# Base-Shield-v2.net
KiCad netlist of a schematic drawn in EAGLE
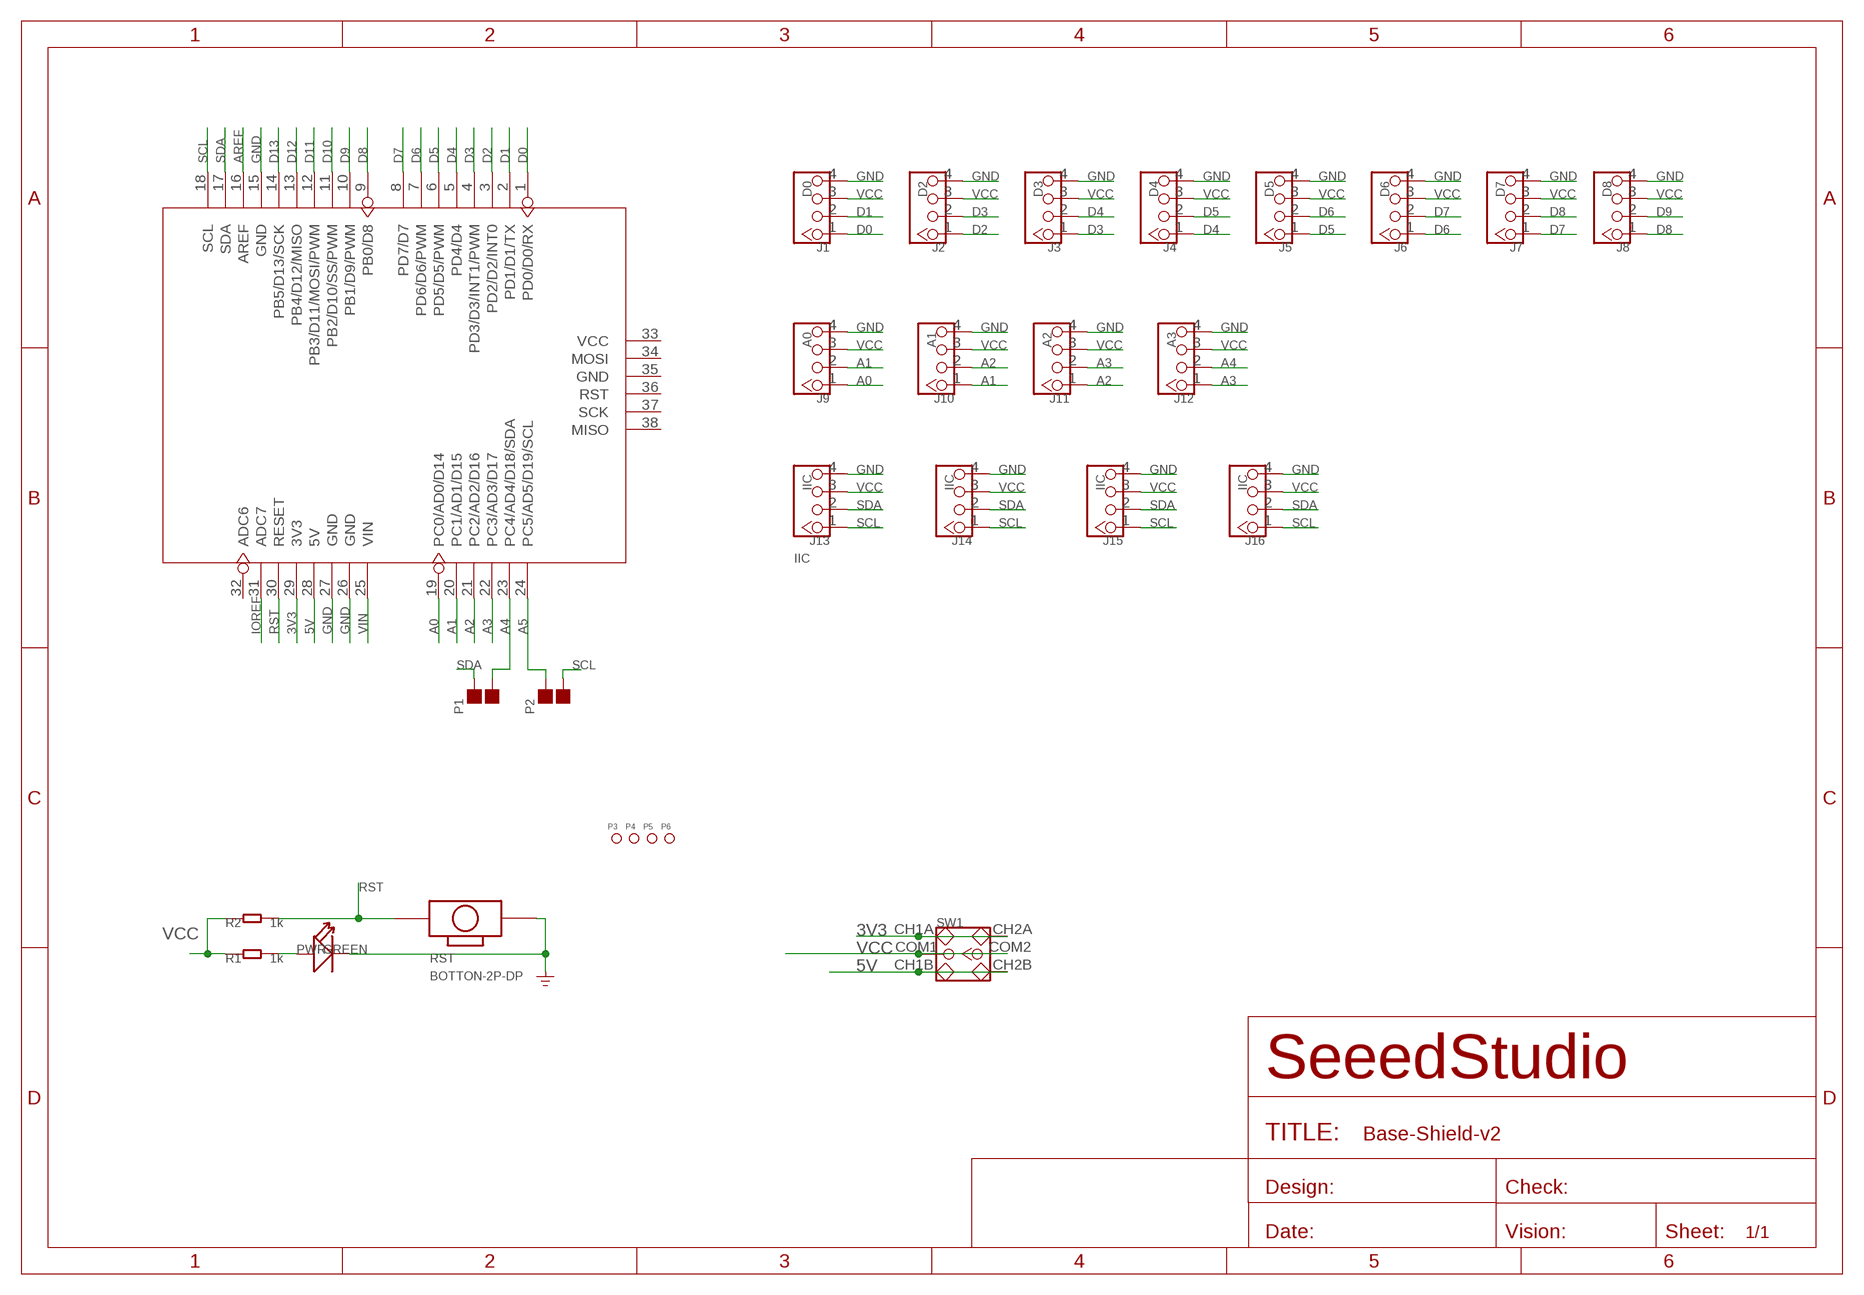
[diagram p0: schematic, sheet 1]

(export (version "E")
  (design (tool "Eeschema 10.0.6"))
  (components
    (comp (ref "J1")
      (value "D0")
      (footprint "eagle-import:4P-2.0")
      (libsource (lib "eagle-import") (part "TWIG-4P-2.0-2.0"))
    )
    (comp (ref "J2")
      (value "D2")
      (footprint "eagle-import:4P-2.0")
      (libsource (lib "eagle-import") (part "TWIG-4P-2.0-2.0"))
    )
    (comp (ref "J3")
      (value "D3")
      (footprint "eagle-import:4P-2.0")
      (libsource (lib "eagle-import") (part "TWIG-4P-2.0-2.0"))
    )
    (comp (ref "J4")
      (value "D4")
      (footprint "eagle-import:4P-2.0")
      (libsource (lib "eagle-import") (part "TWIG-4P-2.0-2.0"))
    )
    (comp (ref "J5")
      (value "D5")
      (footprint "eagle-import:4P-2.0")
      (libsource (lib "eagle-import") (part "TWIG-4P-2.0-2.0"))
    )
    (comp (ref "J6")
      (value "D6")
      (footprint "eagle-import:4P-2.0")
      (libsource (lib "eagle-import") (part "TWIG-4P-2.0-2.0"))
    )
    (comp (ref "J7")
      (value "D7")
      (footprint "eagle-import:4P-2.0")
      (libsource (lib "eagle-import") (part "TWIG-4P-2.0-2.0"))
    )
    (comp (ref "J8")
      (value "D8")
      (footprint "eagle-import:4P-2.0")
      (libsource (lib "eagle-import") (part "TWIG-4P-2.0-2.0"))
    )
    (comp (ref "J9")
      (value "A0")
      (footprint "eagle-import:4P-2.0-90D")
      (libsource (lib "eagle-import") (part "TWIG-4P-2.0'90D'"))
    )
    (comp (ref "J10")
      (value "A1")
      (footprint "eagle-import:4P-2.0-90D")
      (libsource (lib "eagle-import") (part "TWIG-4P-2.0'90D'"))
    )
    (comp (ref "J11")
      (value "A2")
      (footprint "eagle-import:4P-2.0-90D")
      (libsource (lib "eagle-import") (part "TWIG-4P-2.0'90D'"))
    )
    (comp (ref "J12")
      (value "A3")
      (footprint "eagle-import:4P-2.0-90D")
      (libsource (lib "eagle-import") (part "TWIG-4P-2.0'90D'"))
    )
    (comp (ref "J13")
      (value "IIC")
      (footprint "eagle-import:4P-2.0")
      (libsource (lib "eagle-import") (part "TWIG-4P-2.0-2.0"))
    )
    (comp (ref "J14")
      (value "IIC")
      (footprint "eagle-import:4P-2.0")
      (libsource (lib "eagle-import") (part "TWIG-4P-2.0-2.0"))
    )
    (comp (ref "J15")
      (value "IIC")
      (footprint "eagle-import:4P-2.0")
      (libsource (lib "eagle-import") (part "TWIG-4P-2.0-2.0"))
    )
    (comp (ref "J16")
      (value "IIC")
      (footprint "eagle-import:4P-2.0")
      (libsource (lib "eagle-import") (part "TWIG-4P-2.0-2.0"))
    )
    (comp (ref "P1")
      (value "DNP")
      (footprint "eagle-import:2P-SMD-1.78X1.27")
      (libsource (lib "eagle-import") (part "PAD-JUMPER-2P"))
    )
    (comp (ref "P2")
      (value "DNP")
      (footprint "eagle-import:2P-SMD-1.78X1.27")
      (libsource (lib "eagle-import") (part "PAD-JUMPER-2P"))
    )
    (comp (ref "P3")
      (value "PAD-MARK")
      (footprint "eagle-import:ROUND-MARK-1.0")
      (fields (field (name "PARTNO") "DNP"))
      (libsource (lib "eagle-import") (part "PAD-MARK"))
    )
    (comp (ref "P4")
      (value "PAD-MARK")
      (footprint "eagle-import:ROUND-MARK-1.0")
      (fields (field (name "PARTNO") "DNP"))
      (libsource (lib "eagle-import") (part "PAD-MARK"))
    )
    (comp (ref "P5")
      (value "PAD-MARK")
      (footprint "eagle-import:ROUND-MARK-1.0")
      (fields (field (name "PARTNO") "DNP"))
      (libsource (lib "eagle-import") (part "PAD-MARK"))
    )
    (comp (ref "P6")
      (value "PAD-MARK")
      (footprint "eagle-import:ROUND-MARK-1.0")
      (fields (field (name "PARTNO") "DNP"))
      (libsource (lib "eagle-import") (part "PAD-MARK"))
    )
    (comp (ref "PWR")
      (value "GREEN")
      (footprint "eagle-import:LED-2P-2.54-3MM")
      (libsource (lib "eagle-import") (part "LED-3MM"))
    )
    (comp (ref "R1")
      (value "1k")
      (footprint "eagle-import:R0603")
      (libsource (lib "eagle-import") (part "R-0603"))
    )
    (comp (ref "R2")
      (value "1k")
      (footprint "eagle-import:R0603")
      (libsource (lib "eagle-import") (part "R-0603"))
    )
    (comp (ref "RST")
      (value "BOTTON-2P-DP")
      (footprint "eagle-import:2P-7.62X3.56-90D")
      (libsource (lib "eagle-import") (part "BOTTON-2P-90"))
    )
    (comp (ref "SW1")
      (value "SWITCH-2CH-6P'90D'")
      (footprint "eagle-import:6P-2CH-2.5-9.1X3.5X3.2H-90D")
      (libsource (lib "eagle-import") (part "SWITCH-2CH-6P'90D'"))
    )
    (comp (ref "U2")
      (value "DIP Long Blue Female Header")
      (footprint "eagle-import:ARDUINO-38P")
      (libsource (lib "eagle-import") (part "ARDUINO-38P"))
    )
  )
  (nets
    (net (code "1") (name "/3V3") (class "Default")
      (node (ref "SW1") (pin "CH1A") (pinfunction "CH1A_CH1A") (pintype "bidirectional"))
      (node (ref "SW1") (pin "CH2A") (pinfunction "CH2A_CH2A") (pintype "bidirectional"))
      (node (ref "U2") (pin "29") (pinfunction "3V3_29") (pintype "bidirectional"))
    )
    (net (code "2") (name "/5V") (class "Default")
      (node (ref "SW1") (pin "CH1B") (pinfunction "CH1B_CH1B") (pintype "bidirectional"))
      (node (ref "SW1") (pin "CH2B") (pinfunction "CH2B_CH2B") (pintype "bidirectional"))
      (node (ref "U2") (pin "28") (pinfunction "5V_28") (pintype "bidirectional"))
    )
    (net (code "3") (name "/A0") (class "Default")
      (node (ref "J9") (pin "1") (pinfunction "1_1") (pintype "bidirectional"))
      (node (ref "U2") (pin "19") (pinfunction "PC0/AD0/D14_19") (pintype "bidirectional"))
    )
    (net (code "4") (name "/A1") (class "Default")
      (node (ref "J10") (pin "1") (pinfunction "1_1") (pintype "bidirectional"))
      (node (ref "J9") (pin "2") (pinfunction "2_2") (pintype "bidirectional"))
      (node (ref "U2") (pin "20") (pinfunction "PC1/AD1/D15_20") (pintype "bidirectional"))
    )
    (net (code "5") (name "/A2") (class "Default")
      (node (ref "J10") (pin "2") (pinfunction "2_2") (pintype "bidirectional"))
      (node (ref "J11") (pin "1") (pinfunction "1_1") (pintype "bidirectional"))
      (node (ref "U2") (pin "21") (pinfunction "PC2/AD2/D16_21") (pintype "bidirectional"))
    )
    (net (code "6") (name "/A3") (class "Default")
      (node (ref "J11") (pin "2") (pinfunction "2_2") (pintype "bidirectional"))
      (node (ref "J12") (pin "1") (pinfunction "1_1") (pintype "bidirectional"))
      (node (ref "U2") (pin "22") (pinfunction "PC3/AD3/D17_22") (pintype "bidirectional"))
    )
    (net (code "7") (name "/A4") (class "Default")
      (node (ref "J12") (pin "2") (pinfunction "2_2") (pintype "bidirectional"))
      (node (ref "P1") (pin "1") (pinfunction "1_1") (pintype "bidirectional"))
      (node (ref "U2") (pin "23") (pinfunction "PC4/AD4/D18/SDA_23") (pintype "bidirectional"))
    )
    (net (code "8") (name "/A5") (class "Default")
      (node (ref "P2") (pin "2") (pinfunction "2_2") (pintype "bidirectional"))
      (node (ref "U2") (pin "24") (pinfunction "PC5/AD5/D19/SCL_24") (pintype "bidirectional"))
    )
    (net (code "9") (name "/AREF") (class "Default")
      (node (ref "U2") (pin "16") (pinfunction "AREF_16") (pintype "bidirectional"))
    )
    (net (code "10") (name "/D0") (class "Default")
      (node (ref "J1") (pin "1") (pinfunction "1_1") (pintype "bidirectional"))
      (node (ref "U2") (pin "1") (pinfunction "PD0/D0/RX_1") (pintype "bidirectional"))
    )
    (net (code "11") (name "/D1") (class "Default")
      (node (ref "J1") (pin "2") (pinfunction "2_2") (pintype "bidirectional"))
      (node (ref "U2") (pin "2") (pinfunction "PD1/D1/TX_2") (pintype "bidirectional"))
    )
    (net (code "12") (name "/D2") (class "Default")
      (node (ref "J2") (pin "1") (pinfunction "1_1") (pintype "bidirectional"))
      (node (ref "U2") (pin "3") (pinfunction "PD2/D2/INT0_3") (pintype "bidirectional"))
    )
    (net (code "13") (name "/D3") (class "Default")
      (node (ref "J2") (pin "2") (pinfunction "2_2") (pintype "bidirectional"))
      (node (ref "J3") (pin "1") (pinfunction "1_1") (pintype "bidirectional"))
      (node (ref "U2") (pin "4") (pinfunction "PD3/D3/INT1/PWM_4") (pintype "bidirectional"))
    )
    (net (code "14") (name "/D4") (class "Default")
      (node (ref "J3") (pin "2") (pinfunction "2_2") (pintype "bidirectional"))
      (node (ref "J4") (pin "1") (pinfunction "1_1") (pintype "bidirectional"))
      (node (ref "U2") (pin "5") (pinfunction "PD4/D4_5") (pintype "bidirectional"))
    )
    (net (code "15") (name "/D5") (class "Default")
      (node (ref "J4") (pin "2") (pinfunction "2_2") (pintype "bidirectional"))
      (node (ref "J5") (pin "1") (pinfunction "1_1") (pintype "bidirectional"))
      (node (ref "U2") (pin "6") (pinfunction "PD5/D5/PWM_6") (pintype "bidirectional"))
    )
    (net (code "16") (name "/D6") (class "Default")
      (node (ref "J5") (pin "2") (pinfunction "2_2") (pintype "bidirectional"))
      (node (ref "J6") (pin "1") (pinfunction "1_1") (pintype "bidirectional"))
      (node (ref "U2") (pin "7") (pinfunction "PD6/D6/PWM_7") (pintype "bidirectional"))
    )
    (net (code "17") (name "/D7") (class "Default")
      (node (ref "J6") (pin "2") (pinfunction "2_2") (pintype "bidirectional"))
      (node (ref "J7") (pin "1") (pinfunction "1_1") (pintype "bidirectional"))
      (node (ref "U2") (pin "8") (pinfunction "PD7/D7_8") (pintype "bidirectional"))
    )
    (net (code "18") (name "/D8") (class "Default")
      (node (ref "J7") (pin "2") (pinfunction "2_2") (pintype "bidirectional"))
      (node (ref "J8") (pin "1") (pinfunction "1_1") (pintype "bidirectional"))
      (node (ref "U2") (pin "9") (pinfunction "PB0/D8_9") (pintype "bidirectional"))
    )
    (net (code "19") (name "/D9") (class "Default")
      (node (ref "J8") (pin "2") (pinfunction "2_2") (pintype "bidirectional"))
      (node (ref "U2") (pin "10") (pinfunction "PB1/D9/PWM_10") (pintype "bidirectional"))
    )
    (net (code "20") (name "/D10") (class "Default")
      (node (ref "U2") (pin "11") (pinfunction "PB2/D10/SS/PWM_11") (pintype "bidirectional"))
    )
    (net (code "21") (name "/D11") (class "Default")
      (node (ref "U2") (pin "12") (pinfunction "PB3/D11/MOSI/PWM_12") (pintype "bidirectional"))
    )
    (net (code "22") (name "/D12") (class "Default")
      (node (ref "U2") (pin "13") (pinfunction "PB4/D12/MISO_13") (pintype "bidirectional"))
    )
    (net (code "23") (name "/D13") (class "Default")
      (node (ref "U2") (pin "14") (pinfunction "PB5/D13/SCK_14") (pintype "bidirectional"))
    )
    (net (code "24") (name "/IOREF") (class "Default")
      (node (ref "U2") (pin "31") (pinfunction "ADC7_31") (pintype "bidirectional"))
    )
    (net (code "25") (name "/RST") (class "Default")
      (node (ref "R2") (pin "2") (pinfunction "2_2") (pintype "passive"))
      (node (ref "RST") (pin "P$1") (pinfunction "1_P$1") (pintype "bidirectional"))
      (node (ref "U2") (pin "30") (pinfunction "RESET_30") (pintype "bidirectional"))
    )
    (net (code "26") (name "/SCL") (class "Default")
      (node (ref "J13") (pin "1") (pinfunction "1_1") (pintype "bidirectional"))
      (node (ref "J14") (pin "1") (pinfunction "1_1") (pintype "bidirectional"))
      (node (ref "J15") (pin "1") (pinfunction "1_1") (pintype "bidirectional"))
      (node (ref "J16") (pin "1") (pinfunction "1_1") (pintype "bidirectional"))
      (node (ref "P2") (pin "1") (pinfunction "1_1") (pintype "bidirectional"))
      (node (ref "U2") (pin "18") (pinfunction "SCL_18") (pintype "bidirectional"))
    )
    (net (code "27") (name "/SDA") (class "Default")
      (node (ref "J13") (pin "2") (pinfunction "2_2") (pintype "bidirectional"))
      (node (ref "J14") (pin "2") (pinfunction "2_2") (pintype "bidirectional"))
      (node (ref "J15") (pin "2") (pinfunction "2_2") (pintype "bidirectional"))
      (node (ref "J16") (pin "2") (pinfunction "2_2") (pintype "bidirectional"))
      (node (ref "P1") (pin "2") (pinfunction "2_2") (pintype "bidirectional"))
      (node (ref "U2") (pin "17") (pinfunction "SDA_17") (pintype "bidirectional"))
    )
    (net (code "28") (name "/VCC") (class "Default")
      (node (ref "J1") (pin "3") (pinfunction "3_3") (pintype "bidirectional"))
      (node (ref "J10") (pin "3") (pinfunction "3_3") (pintype "bidirectional"))
      (node (ref "J11") (pin "3") (pinfunction "3_3") (pintype "bidirectional"))
      (node (ref "J12") (pin "3") (pinfunction "3_3") (pintype "bidirectional"))
      (node (ref "J13") (pin "3") (pinfunction "3_3") (pintype "bidirectional"))
      (node (ref "J14") (pin "3") (pinfunction "3_3") (pintype "bidirectional"))
      (node (ref "J15") (pin "3") (pinfunction "3_3") (pintype "bidirectional"))
      (node (ref "J16") (pin "3") (pinfunction "3_3") (pintype "bidirectional"))
      (node (ref "J2") (pin "3") (pinfunction "3_3") (pintype "bidirectional"))
      (node (ref "J3") (pin "3") (pinfunction "3_3") (pintype "bidirectional"))
      (node (ref "J4") (pin "3") (pinfunction "3_3") (pintype "bidirectional"))
      (node (ref "J5") (pin "3") (pinfunction "3_3") (pintype "bidirectional"))
      (node (ref "J6") (pin "3") (pinfunction "3_3") (pintype "bidirectional"))
      (node (ref "J7") (pin "3") (pinfunction "3_3") (pintype "bidirectional"))
      (node (ref "J8") (pin "3") (pinfunction "3_3") (pintype "bidirectional"))
      (node (ref "J9") (pin "3") (pinfunction "3_3") (pintype "bidirectional"))
      (node (ref "R1") (pin "1") (pinfunction "1_1") (pintype "passive"))
      (node (ref "R2") (pin "1") (pinfunction "1_1") (pintype "passive"))
      (node (ref "SW1") (pin "COM1") (pinfunction "COM1_COM1") (pintype "bidirectional"))
      (node (ref "SW1") (pin "COM2") (pinfunction "COM2_COM2") (pintype "bidirectional"))
    )
    (net (code "29") (name "/VIN") (class "Default")
      (node (ref "U2") (pin "25") (pinfunction "VIN_25") (pintype "bidirectional"))
    )
    (net (code "30") (name "GND_POWER") (class "Default")
      (node (ref "J1") (pin "4") (pinfunction "4_4") (pintype "bidirectional"))
      (node (ref "J10") (pin "4") (pinfunction "4_4") (pintype "bidirectional"))
      (node (ref "J11") (pin "4") (pinfunction "4_4") (pintype "bidirectional"))
      (node (ref "J12") (pin "4") (pinfunction "4_4") (pintype "bidirectional"))
      (node (ref "J13") (pin "4") (pinfunction "4_4") (pintype "bidirectional"))
      (node (ref "J14") (pin "4") (pinfunction "4_4") (pintype "bidirectional"))
      (node (ref "J15") (pin "4") (pinfunction "4_4") (pintype "bidirectional"))
      (node (ref "J16") (pin "4") (pinfunction "4_4") (pintype "bidirectional"))
      (node (ref "J2") (pin "4") (pinfunction "4_4") (pintype "bidirectional"))
      (node (ref "J3") (pin "4") (pinfunction "4_4") (pintype "bidirectional"))
      (node (ref "J4") (pin "4") (pinfunction "4_4") (pintype "bidirectional"))
      (node (ref "J5") (pin "4") (pinfunction "4_4") (pintype "bidirectional"))
      (node (ref "J6") (pin "4") (pinfunction "4_4") (pintype "bidirectional"))
      (node (ref "J7") (pin "4") (pinfunction "4_4") (pintype "bidirectional"))
      (node (ref "J8") (pin "4") (pinfunction "4_4") (pintype "bidirectional"))
      (node (ref "J9") (pin "4") (pinfunction "4_4") (pintype "bidirectional"))
      (node (ref "PWR") (pin "K") (pinfunction "-_K") (pintype "passive"))
      (node (ref "RST") (pin "P$2") (pinfunction "2_P$2") (pintype "bidirectional"))
      (node (ref "U2") (pin "15") (pinfunction "GND_15") (pintype "bidirectional"))
      (node (ref "U2") (pin "26") (pinfunction "GND_26") (pintype "bidirectional"))
      (node (ref "U2") (pin "27") (pinfunction "GND_27") (pintype "bidirectional"))
    )
    (net (code "31") (name "Net-(PWR-+)") (class "Default")
      (node (ref "PWR") (pin "A") (pinfunction "+_A") (pintype "passive"))
      (node (ref "R1") (pin "2") (pinfunction "2_2") (pintype "passive"))
    )
    (net (code "32") (name "unconnected-(U2-ADC6-Pad32)") (class "Default")
      (node (ref "U2") (pin "32") (pinfunction "ADC6_32") (pintype "bidirectional"))
    )
    (net (code "33") (name "unconnected-(U2-GND-Pad35)") (class "Default")
      (node (ref "U2") (pin "35") (pinfunction "GND_35") (pintype "bidirectional"))
    )
    (net (code "34") (name "unconnected-(U2-MISO-Pad38)") (class "Default")
      (node (ref "U2") (pin "38") (pinfunction "MISO_38") (pintype "bidirectional"))
    )
    (net (code "35") (name "unconnected-(U2-MOSI-Pad34)") (class "Default")
      (node (ref "U2") (pin "34") (pinfunction "MOSI_34") (pintype "bidirectional"))
    )
    (net (code "36") (name "unconnected-(U2-RST-Pad36)") (class "Default")
      (node (ref "U2") (pin "36") (pinfunction "RST_36") (pintype "bidirectional"))
    )
    (net (code "37") (name "unconnected-(U2-SCK-Pad37)") (class "Default")
      (node (ref "U2") (pin "37") (pinfunction "SCK_37") (pintype "bidirectional"))
    )
    (net (code "38") (name "unconnected-(U2-VCC-Pad33)") (class "Default")
      (node (ref "U2") (pin "33") (pinfunction "VCC_33") (pintype "bidirectional"))
    )
  )
)
